# WirelessReceiverTransmitter.net
KiCad netlist of a schematic drawn in Altium Designer
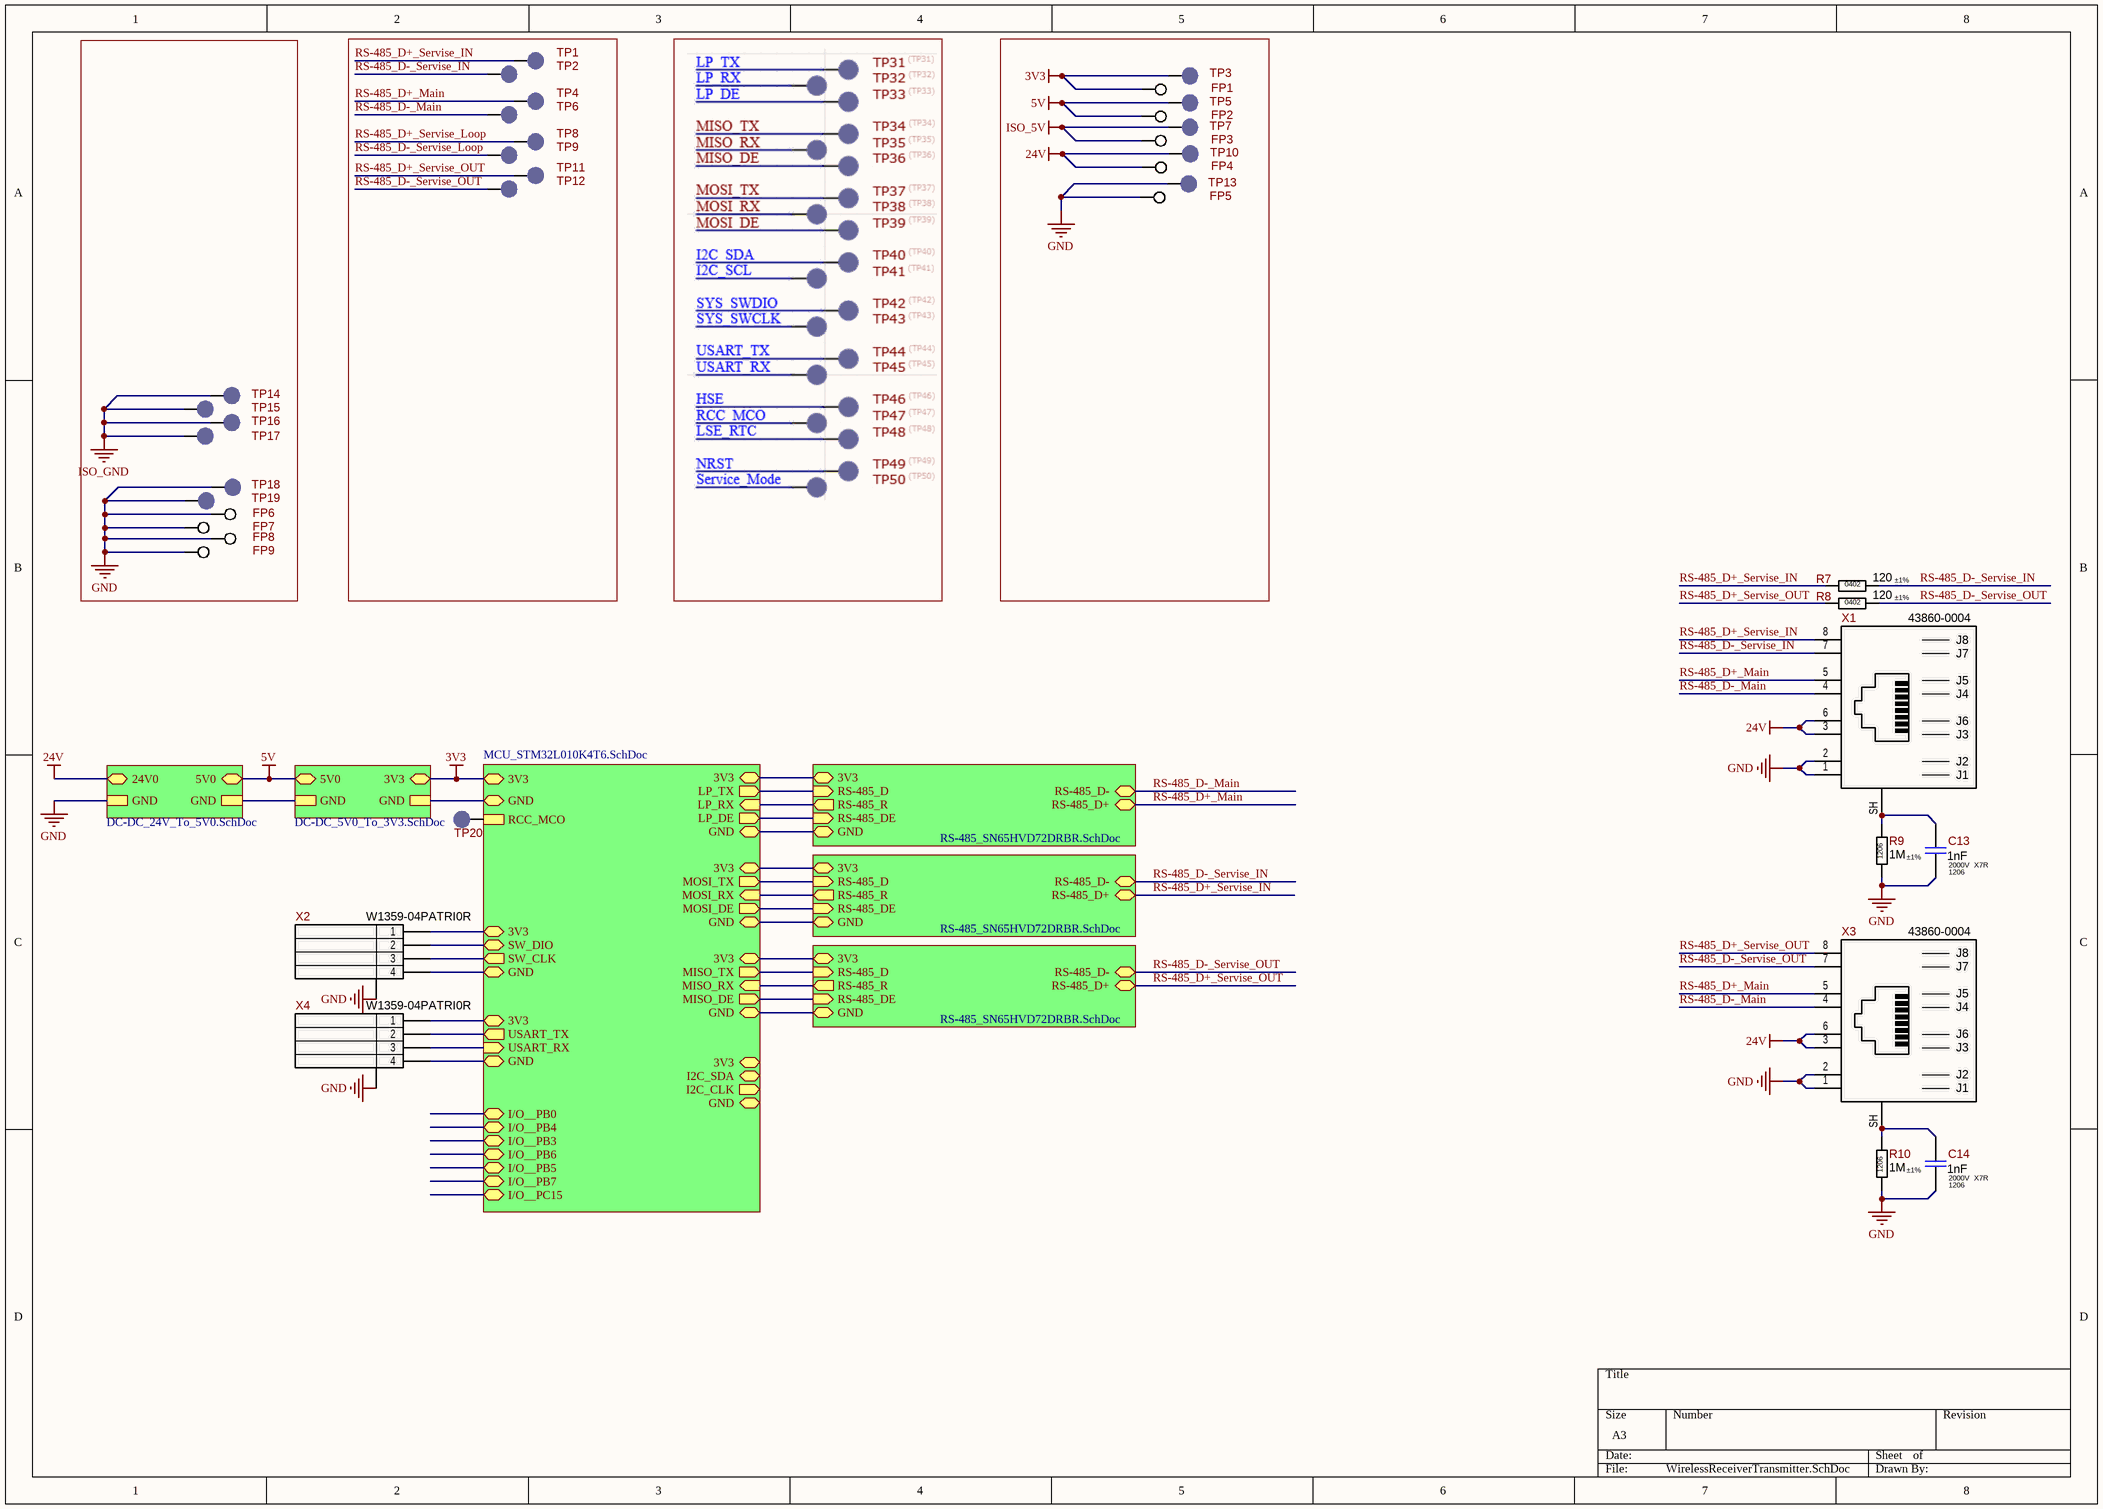
[diagram p0: WirelessReceiverTransmitter.SchDoc]

(export (version "E")
  (design (tool "Eeschema 10.0.6"))
  (components
    (comp (ref "C13")
      (value "1nF")
      (footprint "CAP-1206(3216)X125T20")
      (description "1nF 2000V X7R ±10% 1206 Ceramic Capacitor RoHS")
      (fields
        (field (name "PACKAGE") "1206")
        (field (name "VOLTAGE") "2000V")
        (field (name "DIELECTRIC TYPE") "X7R")
        (field (name "PART NUMBER") "CC1206KKX7RDBB102")
        (field (name "MANUFACTURER") "Yageo")
      )
      (libsource (lib "EL.XXX.T01") (part "Capacitor-NonPolar"))
    )
    (comp (ref "C14")
      (value "1nF")
      (footprint "CAP-1206(3216)X125T20")
      (description "1nF 2000V X7R ±10% 1206 Ceramic Capacitor RoHS")
      (fields
        (field (name "PACKAGE") "1206")
        (field (name "VOLTAGE") "2000V")
        (field (name "DIELECTRIC TYPE") "X7R")
        (field (name "PART NUMBER") "CC1206KKX7RDBB102")
        (field (name "MANUFACTURER") "Yageo")
      )
      (libsource (lib "EL.XXX.T01") (part "Capacitor-NonPolar"))
    )
    (comp (ref "FP1")
      (value "PAD-1.1mm")
      (footprint "PAD-1.1mm")
      (description "1.1mm Pad for Plug-In or Receptacle")
      (fields (field (name "MANUFACTURER") "NONE"))
      (libsource (lib "EL.XXX.T01") (part "Pad"))
    )
    (comp (ref "FP2")
      (value "PAD-1.1mm")
      (footprint "PAD-1.1mm")
      (description "1.1mm Pad for Plug-In or Receptacle")
      (fields (field (name "MANUFACTURER") "NONE"))
      (libsource (lib "EL.XXX.T01") (part "Pad"))
    )
    (comp (ref "FP3")
      (value "PAD-1.1mm")
      (footprint "PAD-1.1mm")
      (description "1.1mm Pad for Plug-In or Receptacle")
      (fields (field (name "MANUFACTURER") "NONE"))
      (libsource (lib "EL.XXX.T01") (part "Pad"))
    )
    (comp (ref "FP4")
      (value "PAD-1.1mm")
      (footprint "PAD-1.1mm")
      (description "1.1mm Pad for Plug-In or Receptacle")
      (fields (field (name "MANUFACTURER") "NONE"))
      (libsource (lib "EL.XXX.T01") (part "Pad"))
    )
    (comp (ref "FP5")
      (value "PAD-1.1mm")
      (footprint "PAD-1.1mm")
      (description "1.1mm Pad for Plug-In or Receptacle")
      (fields (field (name "MANUFACTURER") "NONE"))
      (libsource (lib "EL.XXX.T01") (part "Pad"))
    )
    (comp (ref "FP6")
      (value "PAD-1.1mm")
      (footprint "PAD-1.1mm")
      (description "1.1mm Pad for Plug-In or Receptacle")
      (fields (field (name "MANUFACTURER") "NONE"))
      (libsource (lib "EL.XXX.T01") (part "Pad"))
    )
    (comp (ref "FP7")
      (value "PAD-1.1mm")
      (footprint "PAD-1.1mm")
      (description "1.1mm Pad for Plug-In or Receptacle")
      (fields (field (name "MANUFACTURER") "NONE"))
      (libsource (lib "EL.XXX.T01") (part "Pad"))
    )
    (comp (ref "FP8")
      (value "PAD-1.1mm")
      (footprint "PAD-1.1mm")
      (description "1.1mm Pad for Plug-In or Receptacle")
      (fields (field (name "MANUFACTURER") "NONE"))
      (libsource (lib "EL.XXX.T01") (part "Pad"))
    )
    (comp (ref "FP9")
      (value "PAD-1.1mm")
      (footprint "PAD-1.1mm")
      (description "1.1mm Pad for Plug-In or Receptacle")
      (fields (field (name "MANUFACTURER") "NONE"))
      (libsource (lib "EL.XXX.T01") (part "Pad"))
    )
    (comp (ref "R7")
      (value "120")
      (footprint "R_ANY_CHIP_0402_HI")
      (description "120 Ohms ±1% 1/16W 0402 Thick Film Resistor")
      (fields
        (field (name "TOLERANCE") "±1%")
        (field (name "PACKAGE") "0402")
        (field (name "PART NUMBER") "RC0402FR-07120RL")
        (field (name "MANUFACTURER") "Yageo")
      )
      (libsource (lib "EL.XXX.T01") (part "Resistor"))
    )
    (comp (ref "R8")
      (value "120")
      (footprint "R_ANY_CHIP_0402_HI")
      (description "120 Ohms ±1% 1/16W 0402 Thick Film Resistor")
      (fields
        (field (name "TOLERANCE") "±1%")
        (field (name "PACKAGE") "0402")
        (field (name "PART NUMBER") "RC0402FR-07120RL")
        (field (name "MANUFACTURER") "Yageo")
      )
      (libsource (lib "EL.XXX.T01") (part "Resistor"))
    )
    (comp (ref "R9")
      (value "1M")
      (footprint "CHV1206-Series")
      (description "1 MOhms ±1%, 1/4W 1206 Thick Film Resistor")
      (fields
        (field (name "TOLERANCE") "±1%")
        (field (name "PACKAGE") "1206")
        (field (name "PART NUMBER") "CHV1206-FX-1004ELF")
        (field (name "MANUFACTURER") "Bourns")
      )
      (libsource (lib "EL.XXX.T01") (part "Resistor"))
    )
    (comp (ref "R10")
      (value "1M")
      (footprint "CHV1206-Series")
      (description "1 MOhms ±1%, 1/4W 1206 Thick Film Resistor")
      (fields
        (field (name "TOLERANCE") "±1%")
        (field (name "PACKAGE") "1206")
        (field (name "PART NUMBER") "CHV1206-FX-1004ELF")
        (field (name "MANUFACTURER") "Bourns")
      )
      (libsource (lib "EL.XXX.T01") (part "Resistor"))
    )
    (comp (ref "TP1")
      (value "LED_LINK")
      (footprint "TP_SMD_2mm")
      (description "Test Point SMD Pad 1.0mm/1.5mm/2mm")
      (fields (field (name "PART NUMBER") "TP-PAD-SMD"))
      (libsource (lib "EL.XXX.T01") (part "Test-Point-SMD-1"))
    )
    (comp (ref "TP2")
      (value "LED_LINK")
      (footprint "TP_SMD_2mm")
      (description "Test Point SMD Pad 1.0mm/1.5mm/2mm")
      (fields (field (name "PART NUMBER") "TP-PAD-SMD"))
      (libsource (lib "EL.XXX.T01") (part "Test-Point-SMD-1"))
    )
    (comp (ref "TP3")
      (value "LED_LINK")
      (footprint "TP_SMD_2mm")
      (description "Test Point SMD Pad 1.0mm/1.5mm/2mm")
      (fields (field (name "PART NUMBER") "TP-PAD-SMD"))
      (libsource (lib "EL.XXX.T01") (part "Test-Point-SMD-1"))
    )
    (comp (ref "TP4")
      (value "LED_LINK")
      (footprint "TP_SMD_2mm")
      (description "Test Point SMD Pad 1.0mm/1.5mm/2mm")
      (fields (field (name "PART NUMBER") "TP-PAD-SMD"))
      (libsource (lib "EL.XXX.T01") (part "Test-Point-SMD-1"))
    )
    (comp (ref "TP5")
      (value "LED_LINK")
      (footprint "TP_SMD_2mm")
      (description "Test Point SMD Pad 1.0mm/1.5mm/2mm")
      (fields (field (name "PART NUMBER") "TP-PAD-SMD"))
      (libsource (lib "EL.XXX.T01") (part "Test-Point-SMD-1"))
    )
    (comp (ref "TP6")
      (value "LED_LINK")
      (footprint "TP_SMD_2mm")
      (description "Test Point SMD Pad 1.0mm/1.5mm/2mm")
      (fields (field (name "PART NUMBER") "TP-PAD-SMD"))
      (libsource (lib "EL.XXX.T01") (part "Test-Point-SMD-1"))
    )
    (comp (ref "TP7")
      (value "LED_LINK")
      (footprint "TP_SMD_2mm")
      (description "Test Point SMD Pad 1.0mm/1.5mm/2mm")
      (fields (field (name "PART NUMBER") "TP-PAD-SMD"))
      (libsource (lib "EL.XXX.T01") (part "Test-Point-SMD-1"))
    )
    (comp (ref "TP8")
      (value "LED_LINK")
      (footprint "TP_SMD_2mm")
      (description "Test Point SMD Pad 1.0mm/1.5mm/2mm")
      (fields (field (name "PART NUMBER") "TP-PAD-SMD"))
      (libsource (lib "EL.XXX.T01") (part "Test-Point-SMD-1"))
    )
    (comp (ref "TP9")
      (value "LED_LINK")
      (footprint "TP_SMD_2mm")
      (description "Test Point SMD Pad 1.0mm/1.5mm/2mm")
      (fields (field (name "PART NUMBER") "TP-PAD-SMD"))
      (libsource (lib "EL.XXX.T01") (part "Test-Point-SMD-1"))
    )
    (comp (ref "TP10")
      (value "LED_LINK")
      (footprint "TP_SMD_2mm")
      (description "Test Point SMD Pad 1.0mm/1.5mm/2mm")
      (fields (field (name "PART NUMBER") "TP-PAD-SMD"))
      (libsource (lib "EL.XXX.T01") (part "Test-Point-SMD-1"))
    )
    (comp (ref "TP11")
      (value "LED_LINK")
      (footprint "TP_SMD_2mm")
      (description "Test Point SMD Pad 1.0mm/1.5mm/2mm")
      (fields (field (name "PART NUMBER") "TP-PAD-SMD"))
      (libsource (lib "EL.XXX.T01") (part "Test-Point-SMD-1"))
    )
    (comp (ref "TP12")
      (value "LED_LINK")
      (footprint "TP_SMD_2mm")
      (description "Test Point SMD Pad 1.0mm/1.5mm/2mm")
      (fields (field (name "PART NUMBER") "TP-PAD-SMD"))
      (libsource (lib "EL.XXX.T01") (part "Test-Point-SMD-1"))
    )
    (comp (ref "TP13")
      (value "LED_LINK")
      (footprint "TP_SMD_2mm")
      (description "Test Point SMD Pad 1.0mm/1.5mm/2mm")
      (fields (field (name "PART NUMBER") "TP-PAD-SMD"))
      (libsource (lib "EL.XXX.T01") (part "Test-Point-SMD-1"))
    )
    (comp (ref "TP14")
      (value "LED_LINK")
      (footprint "TP_SMD_2mm")
      (description "Test Point SMD Pad 1.0mm/1.5mm/2mm")
      (fields (field (name "PART NUMBER") "TP-PAD-SMD"))
      (libsource (lib "EL.XXX.T01") (part "Test-Point-SMD-1"))
    )
    (comp (ref "TP15")
      (value "LED_LINK")
      (footprint "TP_SMD_2mm")
      (description "Test Point SMD Pad 1.0mm/1.5mm/2mm")
      (fields (field (name "PART NUMBER") "TP-PAD-SMD"))
      (libsource (lib "EL.XXX.T01") (part "Test-Point-SMD-1"))
    )
    (comp (ref "TP16")
      (value "LED_LINK")
      (footprint "TP_SMD_2mm")
      (description "Test Point SMD Pad 1.0mm/1.5mm/2mm")
      (fields (field (name "PART NUMBER") "TP-PAD-SMD"))
      (libsource (lib "EL.XXX.T01") (part "Test-Point-SMD-1"))
    )
    (comp (ref "TP17")
      (value "LED_LINK")
      (footprint "TP_SMD_2mm")
      (description "Test Point SMD Pad 1.0mm/1.5mm/2mm")
      (fields (field (name "PART NUMBER") "TP-PAD-SMD"))
      (libsource (lib "EL.XXX.T01") (part "Test-Point-SMD-1"))
    )
    (comp (ref "TP18")
      (value "LED_LINK")
      (footprint "TP_SMD_2mm")
      (description "Test Point SMD Pad 1.0mm/1.5mm/2mm")
      (fields (field (name "PART NUMBER") "TP-PAD-SMD"))
      (libsource (lib "EL.XXX.T01") (part "Test-Point-SMD-1"))
    )
    (comp (ref "TP19")
      (value "LED_LINK")
      (footprint "TP_SMD_2mm")
      (description "Test Point SMD Pad 1.0mm/1.5mm/2mm")
      (fields (field (name "PART NUMBER") "TP-PAD-SMD"))
      (libsource (lib "EL.XXX.T01") (part "Test-Point-SMD-1"))
    )
    (comp (ref "TP20")
      (value "LED_LINK")
      (footprint "TP_SMD_2mm")
      (description "Test Point SMD Pad 1.0mm/1.5mm/2mm")
      (fields (field (name "PART NUMBER") "TP-PAD-SMD"))
      (libsource (lib "EL.XXX.T01") (part "Test-Point-SMD-1"))
    )
    (comp (ref "X1")
      (value "43860-0004")
      (footprint "43860-0004")
      (description "RJ45 8P8C Shielded Cat 3 10 Base-T Connector")
      (fields (field (name "PART NUMBER") "43860-0004") (field (name "MANUFACTURER") "Molex"))
      (libsource (lib "EL.XXX.T01") (part "43860-0004"))
    )
    (comp (ref "X2")
      (value "W1359-04PATRI0R")
      (footprint "W1359-04PATXI0R_DBG")
      (description "1.25mm Wire-to-Board Header, Vertical, SMT, 4 pin")
      (fields
        (field (name "PART NUMBER") "W1359-04PATRI0R")
        (field (name "MANUFACTURER") "Hsuan Mao Technology")
      )
      (libsource (lib "EL.XXX.T01") (part "General-4-Pin-MP"))
    )
    (comp (ref "X3")
      (value "43860-0004")
      (footprint "43860-0004")
      (description "RJ45 8P8C Shielded Cat 3 10 Base-T Connector")
      (fields (field (name "PART NUMBER") "43860-0004") (field (name "MANUFACTURER") "Molex"))
      (libsource (lib "EL.XXX.T01") (part "43860-0004"))
    )
    (comp (ref "X4")
      (value "W1359-04PATRI0R")
      (footprint "W1359-04PATXI0R_DBG")
      (description "1.25mm Wire-to-Board Header, Vertical, SMT, 4 pin")
      (fields
        (field (name "PART NUMBER") "W1359-04PATRI0R")
        (field (name "MANUFACTURER") "Hsuan Mao Technology")
      )
      (libsource (lib "EL.XXX.T01") (part "General-4-Pin-MP"))
    )
  )
  (nets
    (net (code "5") (name "/3V3_4") (class "Default")
      (node (ref "X2") (pin "1") (pinfunction "1_1") (pintype "passive"))
    )
    (net (code "7") (name "/3V3_6") (class "Default")
      (node (ref "X4") (pin "1") (pinfunction "1_1") (pintype "passive"))
    )
    (net (code "15") (name "/GND_5") (class "Default")
      (node (ref "X4") (pin "4") (pinfunction "4_4") (pintype "passive"))
    )
    (net (code "20") (name "/GND_10") (class "Default")
      (node (ref "X2") (pin "4") (pinfunction "4_4") (pintype "passive"))
    )
    (net (code "39") (name "/RCC_MCO") (class "Default") (node (ref "TP20") (pin "1") (pintype "passive")))
    (net (code "41") (name "/RS-485_D+_Main") (class "Default")
      (node (ref "TP4") (pin "1") (pintype "passive"))
      (node (ref "X1") (pin "5") (pinfunction "CT_5") (pintype "passive"))
      (node (ref "X3") (pin "5") (pinfunction "CT_5") (pintype "passive"))
    )
    (net (code "42") (name "/RS-485_D+_Servise_IN") (class "Default")
      (node (ref "R7") (pin "1") (pintype "passive"))
      (node (ref "TP1") (pin "1") (pintype "passive"))
      (node (ref "X1") (pin "8") (pinfunction "TD2+_8") (pintype "passive"))
    )
    (net (code "43") (name "/RS-485_D+_Servise_Loop") (class "Default")
      (node (ref "TP8") (pin "1") (pintype "passive"))
    )
    (net (code "44") (name "/RS-485_D+_Servise_OUT") (class "Default")
      (node (ref "R8") (pin "1") (pintype "passive"))
      (node (ref "TP11") (pin "1") (pintype "passive"))
      (node (ref "X3") (pin "8") (pinfunction "TD2+_8") (pintype "passive"))
    )
    (net (code "45") (name "/RS-485_D-_Main") (class "Default")
      (node (ref "TP6") (pin "1") (pintype "passive"))
      (node (ref "X1") (pin "4") (pinfunction "TD3+_4") (pintype "passive"))
      (node (ref "X3") (pin "4") (pinfunction "TD3+_4") (pintype "passive"))
    )
    (net (code "46") (name "/RS-485_D-_Servise_IN") (class "Default")
      (node (ref "R7") (pin "2") (pintype "passive"))
      (node (ref "TP2") (pin "1") (pintype "passive"))
      (node (ref "X1") (pin "7") (pinfunction "TD2-_7") (pintype "passive"))
    )
    (net (code "47") (name "/RS-485_D-_Servise_Loop") (class "Default")
      (node (ref "TP9") (pin "1") (pintype "passive"))
    )
    (net (code "48") (name "/RS-485_D-_Servise_OUT") (class "Default")
      (node (ref "R8") (pin "2") (pintype "passive"))
      (node (ref "TP12") (pin "1") (pintype "passive"))
      (node (ref "X3") (pin "7") (pinfunction "TD2-_7") (pintype "passive"))
    )
    (net (code "57") (name "/SW_CLK") (class "Default")
      (node (ref "X2") (pin "3") (pinfunction "3_3") (pintype "passive"))
    )
    (net (code "58") (name "/SW_DIO") (class "Default")
      (node (ref "X2") (pin "2") (pinfunction "2_2") (pintype "passive"))
    )
    (net (code "59") (name "/USART_RX") (class "Default")
      (node (ref "X4") (pin "3") (pinfunction "3_3") (pintype "passive"))
    )
    (net (code "60") (name "/USART_TX") (class "Default")
      (node (ref "X4") (pin "2") (pinfunction "2_2") (pintype "passive"))
    )
    (net (code "61") (name "3V3") (class "Default")
      (node (ref "FP1") (pin "1") (pintype "passive"))
      (node (ref "TP3") (pin "1") (pintype "passive"))
    )
    (net (code "62") (name "5V") (class "Default")
      (node (ref "FP2") (pin "1") (pintype "passive"))
      (node (ref "TP5") (pin "1") (pintype "passive"))
    )
    (net (code "63") (name "24V") (class "Default")
      (node (ref "FP4") (pin "1") (pintype "passive"))
      (node (ref "TP10") (pin "1") (pintype "passive"))
      (node (ref "X1") (pin "3") (pinfunction "TD3-_3") (pintype "passive"))
      (node (ref "X1") (pin "6") (pinfunction "CT_6") (pintype "passive"))
      (node (ref "X3") (pin "3") (pinfunction "TD3-_3") (pintype "passive"))
      (node (ref "X3") (pin "6") (pinfunction "CT_6") (pintype "passive"))
    )
    (net (code "64") (name "GND") (class "Default")
      (node (ref "C13") (pin "2") (pinfunction "2_2") (pintype "passive"))
      (node (ref "C14") (pin "2") (pinfunction "2_2") (pintype "passive"))
      (node (ref "FP5") (pin "1") (pintype "passive"))
      (node (ref "FP6") (pin "1") (pintype "passive"))
      (node (ref "FP7") (pin "1") (pintype "passive"))
      (node (ref "FP8") (pin "1") (pintype "passive"))
      (node (ref "FP9") (pin "1") (pintype "passive"))
      (node (ref "R10") (pin "2") (pintype "passive"))
      (node (ref "R9") (pin "2") (pintype "passive"))
      (node (ref "TP13") (pin "1") (pintype "passive"))
      (node (ref "TP18") (pin "1") (pintype "passive"))
      (node (ref "TP19") (pin "1") (pintype "passive"))
      (node (ref "X1") (pin "1") (pinfunction "TD4-_1") (pintype "passive"))
      (node (ref "X1") (pin "2") (pinfunction "TD4+_2") (pintype "passive"))
      (node (ref "X2") (pin "MP") (pinfunction "MountPad_MP") (pintype "passive"))
      (node (ref "X3") (pin "1") (pinfunction "TD4-_1") (pintype "passive"))
      (node (ref "X3") (pin "2") (pinfunction "TD4+_2") (pintype "passive"))
      (node (ref "X4") (pin "MP") (pinfunction "MountPad_MP") (pintype "passive"))
    )
    (net (code "65") (name "ISO_5V") (class "Default")
      (node (ref "FP3") (pin "1") (pintype "passive"))
      (node (ref "TP7") (pin "1") (pintype "passive"))
    )
    (net (code "66") (name "ISO_GND") (class "Default")
      (node (ref "TP14") (pin "1") (pintype "passive"))
      (node (ref "TP15") (pin "1") (pintype "passive"))
      (node (ref "TP16") (pin "1") (pintype "passive"))
      (node (ref "TP17") (pin "1") (pintype "passive"))
    )
    (net (code "67") (name "Net-(X1-Shield)") (class "Default")
      (node (ref "C13") (pin "1") (pinfunction "1_1") (pintype "passive"))
      (node (ref "R9") (pin "1") (pintype "passive"))
      (node (ref "X1") (pin "SH") (pinfunction "Shield_SH") (pintype "passive"))
    )
    (net (code "68") (name "Net-(X3-Shield)") (class "Default")
      (node (ref "C14") (pin "1") (pinfunction "1_1") (pintype "passive"))
      (node (ref "R10") (pin "1") (pintype "passive"))
      (node (ref "X3") (pin "SH") (pinfunction "Shield_SH") (pintype "passive"))
    )
  )
)
